# dspic.net
KiCad netlist of a schematic drawn in EAGLE
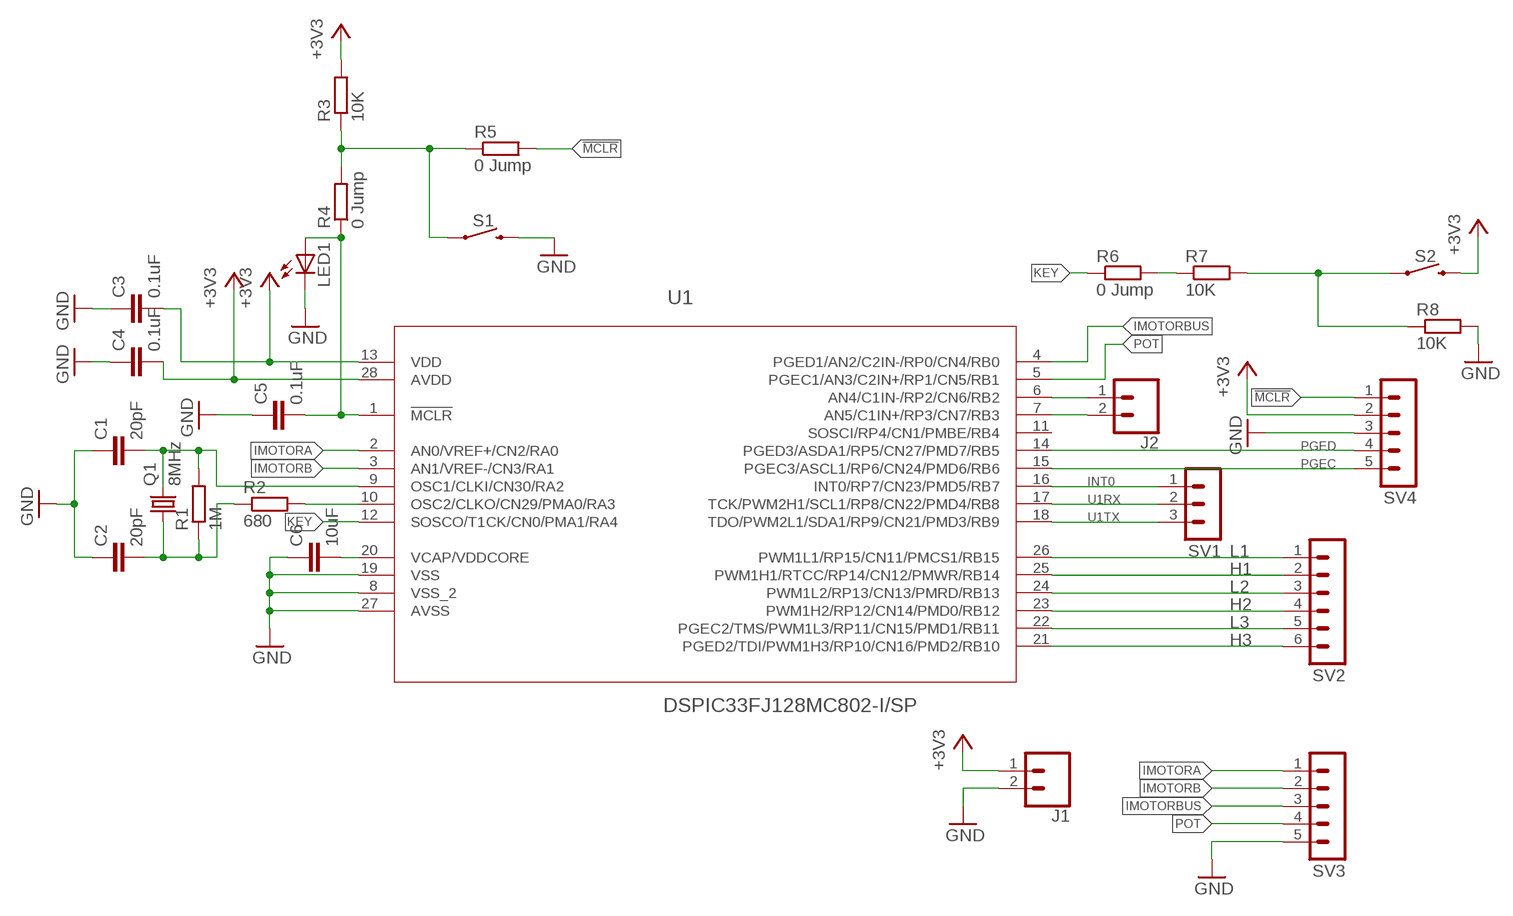
[diagram p0: schematic, sheet 1]

(export (version "E")
  (design (tool "Eeschema 10.0.6"))
  (components
    (comp (ref "C1")
      (value "20pF")
      (footprint "eagle-import:C025-024X044")
      (libsource (lib "eagle-import") (part "C-EU025-024X044"))
    )
    (comp (ref "C2")
      (value "20pF")
      (footprint "eagle-import:C025-024X044")
      (libsource (lib "eagle-import") (part "C-EU025-024X044"))
    )
    (comp (ref "C3")
      (value "0.1uF")
      (footprint "eagle-import:C025-024X044")
      (libsource (lib "eagle-import") (part "C-EU025-024X044"))
    )
    (comp (ref "C4")
      (value "0.1uF")
      (footprint "eagle-import:C025-024X044")
      (libsource (lib "eagle-import") (part "C-EU025-024X044"))
    )
    (comp (ref "C5")
      (value "0.1uF")
      (footprint "eagle-import:C025-024X044")
      (libsource (lib "eagle-import") (part "C-EU025-024X044"))
    )
    (comp (ref "C6")
      (value "10uF")
      (footprint "eagle-import:C025-024X044")
      (libsource (lib "eagle-import") (part "C-EU025-024X044"))
    )
    (comp (ref "J1")
      (value "CONN_02")
      (footprint "eagle-import:1X02")
      (libsource (lib "eagle-import") (part "CONN_02"))
    )
    (comp (ref "J2")
      (value "CONN_02")
      (footprint "eagle-import:1X02")
      (libsource (lib "eagle-import") (part "CONN_02"))
    )
    (comp (ref "LED1")
      (value "LED3MM")
      (footprint "eagle-import:LED3MM")
      (libsource (lib "eagle-import") (part "LED3MM"))
    )
    (comp (ref "Q1")
      (value "8MHz")
      (footprint "eagle-import:HC49_S")
      (libsource (lib "eagle-import") (part "CRYSTALHC49S"))
    )
    (comp (ref "R1")
      (value "1M")
      (footprint "eagle-import:0207_10")
      (libsource (lib "eagle-import") (part "R-EU_0207/10"))
    )
    (comp (ref "R2")
      (value "680")
      (footprint "eagle-import:0207_10")
      (libsource (lib "eagle-import") (part "R-EU_0207/10"))
    )
    (comp (ref "R3")
      (value "10K")
      (footprint "eagle-import:0207_10")
      (libsource (lib "eagle-import") (part "R-EU_0207/10"))
    )
    (comp (ref "R4")
      (value "0 Jump")
      (footprint "eagle-import:0207_10")
      (libsource (lib "eagle-import") (part "R-EU_0207/10"))
    )
    (comp (ref "R5")
      (value "0 Jump")
      (footprint "eagle-import:0207_10")
      (libsource (lib "eagle-import") (part "R-EU_0207/10"))
    )
    (comp (ref "R6")
      (value "0 Jump")
      (footprint "eagle-import:0207_10")
      (libsource (lib "eagle-import") (part "R-EU_0207/10"))
    )
    (comp (ref "R7")
      (value "10K")
      (footprint "eagle-import:0207_10")
      (libsource (lib "eagle-import") (part "R-EU_0207/10"))
    )
    (comp (ref "R8")
      (value "10K")
      (footprint "eagle-import:0207_10")
      (libsource (lib "eagle-import") (part "R-EU_0207/10"))
    )
    (comp (ref "S1")
      (value "MOMENTARY-SWITCH-SPST-PTH-6.0MM")
      (footprint "eagle-import:TACTILE_SWITCH_PTH_6.0MM")
      (libsource (lib "eagle-import") (part "MOMENTARY-SWITCH-SPST-PTH-6.0MM"))
    )
    (comp (ref "S2")
      (value "MOMENTARY-SWITCH-SPST-PTH-6.0MM")
      (footprint "eagle-import:TACTILE_SWITCH_PTH_6.0MM")
      (libsource (lib "eagle-import") (part "MOMENTARY-SWITCH-SPST-PTH-6.0MM"))
    )
    (comp (ref "SV1")
      (value "MA03-1")
      (footprint "eagle-import:MA03-1")
      (libsource (lib "eagle-import") (part "MA03-1"))
    )
    (comp (ref "SV2")
      (value "MA06-1")
      (footprint "eagle-import:MA06-1")
      (libsource (lib "eagle-import") (part "MA06-1"))
    )
    (comp (ref "SV3")
      (value "MA05-1")
      (footprint "eagle-import:MA05-1")
      (libsource (lib "eagle-import") (part "MA05-1"))
    )
    (comp (ref "SV4")
      (value "MA05-1")
      (footprint "eagle-import:MA05-1")
      (libsource (lib "eagle-import") (part "MA05-1"))
    )
    (comp (ref "U1")
      (value "DSPIC33FJ128MC802-I/SP")
      (footprint "eagle-import:DIP254P762X508-28")
      (libsource (lib "eagle-import") (part "DSPIC33FJ128MC802-I/SP"))
    )
  )
  (nets
    (net (code "1") (name "+3V3") (class "Default")
      (node (ref "C3") (pin "2") (pinfunction "2_2") (pintype "passive"))
      (node (ref "C4") (pin "2") (pinfunction "2_2") (pintype "passive"))
      (node (ref "J1") (pin "1") (pinfunction "1_1") (pintype "passive"))
      (node (ref "R3") (pin "2") (pinfunction "2_2") (pintype "passive"))
      (node (ref "S2") (pin "3") (pinfunction "2_3") (pintype "passive"))
      (node (ref "SV4") (pin "2") (pinfunction "2_2") (pintype "passive"))
      (node (ref "U1") (pin "13") (pinfunction "VDD_13") (pintype "power_in"))
      (node (ref "U1") (pin "28") (pinfunction "AVDD_28") (pintype "power_in"))
    )
    (net (code "2") (name "/H1") (class "Default")
      (node (ref "SV2") (pin "2") (pinfunction "2_2") (pintype "passive"))
      (node (ref "U1") (pin "25") (pinfunction "PWM1H1/RTCC/RP14/CN12/PMWR/RB14_25") (pintype "bidirectional"))
    )
    (net (code "3") (name "/H2") (class "Default")
      (node (ref "SV2") (pin "4") (pinfunction "4_4") (pintype "passive"))
      (node (ref "U1") (pin "23") (pinfunction "PWM1H2/RP12/CN14/PMD0/RB12_23") (pintype "bidirectional"))
    )
    (net (code "4") (name "/H3") (class "Default")
      (node (ref "SV2") (pin "6") (pinfunction "6_6") (pintype "passive"))
      (node (ref "U1") (pin "21") (pinfunction "PGED2/TDI/PWM1H3/RP10/CN16/PMD2/RB10_21") (pintype "bidirectional"))
    )
    (net (code "5") (name "/INT0") (class "Default")
      (node (ref "SV1") (pin "1") (pinfunction "1_1") (pintype "passive"))
      (node (ref "U1") (pin "16") (pinfunction "INT0/RP7/CN23/PMD5/RB7_16") (pintype "bidirectional"))
    )
    (net (code "6") (name "/L1") (class "Default")
      (node (ref "SV2") (pin "1") (pinfunction "1_1") (pintype "passive"))
      (node (ref "U1") (pin "26") (pinfunction "PWM1L1/RP15/CN11/PMCS1/RB15_26") (pintype "bidirectional"))
    )
    (net (code "7") (name "/L2") (class "Default")
      (node (ref "SV2") (pin "3") (pinfunction "3_3") (pintype "passive"))
      (node (ref "U1") (pin "24") (pinfunction "PWM1L2/RP13/CN13/PMRD/RB13_24") (pintype "bidirectional"))
    )
    (net (code "8") (name "/L3") (class "Default")
      (node (ref "SV2") (pin "5") (pinfunction "5_5") (pintype "passive"))
      (node (ref "U1") (pin "22") (pinfunction "PGEC2/TMS/PWM1L3/RP11/CN15/PMD1/RB11_22") (pintype "bidirectional"))
    )
    (net (code "9") (name "/PGEC") (class "Default")
      (node (ref "SV4") (pin "5") (pinfunction "5_5") (pintype "passive"))
      (node (ref "U1") (pin "15") (pinfunction "PGEC3/ASCL1/RP6/CN24/PMD6/RB6_15") (pintype "bidirectional"))
    )
    (net (code "10") (name "/PGED") (class "Default")
      (node (ref "SV4") (pin "4") (pinfunction "4_4") (pintype "passive"))
      (node (ref "U1") (pin "14") (pinfunction "PGED3/ASDA1/RP5/CN27/PMD7/RB5_14") (pintype "bidirectional"))
    )
    (net (code "11") (name "/U1RX") (class "Default")
      (node (ref "SV1") (pin "2") (pinfunction "2_2") (pintype "passive"))
      (node (ref "U1") (pin "17") (pinfunction "TCK/PWM2H1/SCL1/RP8/CN22/PMD4/RB8_17") (pintype "bidirectional"))
    )
    (net (code "12") (name "/U1TX") (class "Default")
      (node (ref "SV1") (pin "3") (pinfunction "3_3") (pintype "passive"))
      (node (ref "U1") (pin "18") (pinfunction "TDO/PWM2L1/SDA1/RP9/CN21/PMD3/RB9_18") (pintype "bidirectional"))
    )
    (net (code "13") (name "/~{MCLR}") (class "Default")
      (node (ref "R5") (pin "2") (pinfunction "2_2") (pintype "passive"))
      (node (ref "SV4") (pin "1") (pinfunction "1_1") (pintype "passive"))
    )
    (net (code "14") (name "GND") (class "Default")
      (node (ref "C1") (pin "1") (pinfunction "1_1") (pintype "passive"))
      (node (ref "C2") (pin "1") (pinfunction "1_1") (pintype "passive"))
      (node (ref "C3") (pin "1") (pinfunction "1_1") (pintype "passive"))
      (node (ref "C4") (pin "1") (pinfunction "1_1") (pintype "passive"))
      (node (ref "C5") (pin "1") (pinfunction "1_1") (pintype "passive"))
      (node (ref "C6") (pin "1") (pinfunction "1_1") (pintype "passive"))
      (node (ref "J1") (pin "2") (pinfunction "2_2") (pintype "passive"))
      (node (ref "LED1") (pin "K") (pinfunction "C_K") (pintype "passive"))
      (node (ref "R8") (pin "2") (pinfunction "2_2") (pintype "passive"))
      (node (ref "S1") (pin "3") (pinfunction "2_3") (pintype "passive"))
      (node (ref "SV3") (pin "5") (pinfunction "5_5") (pintype "passive"))
      (node (ref "SV4") (pin "3") (pinfunction "3_3") (pintype "passive"))
      (node (ref "U1") (pin "19") (pinfunction "VSS_19") (pintype "power_in"))
      (node (ref "U1") (pin "27") (pinfunction "AVSS_27") (pintype "power_in"))
      (node (ref "U1") (pin "8") (pinfunction "VSS_2_8") (pintype "power_in"))
    )
    (net (code "15") (name "IMOTORA") (class "Default")
      (node (ref "SV3") (pin "1") (pinfunction "1_1") (pintype "passive"))
      (node (ref "U1") (pin "2") (pinfunction "AN0/VREF+/CN2/RA0_2") (pintype "bidirectional"))
    )
    (net (code "16") (name "IMOTORB") (class "Default")
      (node (ref "SV3") (pin "2") (pinfunction "2_2") (pintype "passive"))
      (node (ref "U1") (pin "3") (pinfunction "AN1/VREF-/CN3/RA1_3") (pintype "bidirectional"))
    )
    (net (code "17") (name "IMOTORBUS") (class "Default")
      (node (ref "SV3") (pin "3") (pinfunction "3_3") (pintype "passive"))
      (node (ref "U1") (pin "4") (pinfunction "PGED1/AN2/C2IN-/RP0/CN4/RB0_4") (pintype "bidirectional"))
    )
    (net (code "18") (name "KEY") (class "Default")
      (node (ref "R6") (pin "1") (pinfunction "1_1") (pintype "passive"))
      (node (ref "U1") (pin "12") (pinfunction "SOSCO/T1CK/CN0/PMA1/RA4_12") (pintype "bidirectional"))
    )
    (net (code "19") (name "Net-(C2-Pad2)") (class "Default")
      (node (ref "C2") (pin "2") (pinfunction "2_2") (pintype "passive"))
      (node (ref "Q1") (pin "1") (pinfunction "1_1") (pintype "passive"))
      (node (ref "R1") (pin "1") (pinfunction "1_1") (pintype "passive"))
      (node (ref "R2") (pin "1") (pinfunction "1_1") (pintype "passive"))
    )
    (net (code "20") (name "Net-(R3-Pad1)") (class "Default")
      (node (ref "R3") (pin "1") (pinfunction "1_1") (pintype "passive"))
      (node (ref "R4") (pin "2") (pinfunction "2_2") (pintype "passive"))
      (node (ref "R5") (pin "1") (pinfunction "1_1") (pintype "passive"))
      (node (ref "S1") (pin "1") (pinfunction "1_1") (pintype "passive"))
    )
    (net (code "21") (name "Net-(R6-Pad2)") (class "Default")
      (node (ref "R6") (pin "2") (pinfunction "2_2") (pintype "passive"))
      (node (ref "R7") (pin "1") (pinfunction "1_1") (pintype "passive"))
    )
    (net (code "22") (name "Net-(R7-Pad2)") (class "Default")
      (node (ref "R7") (pin "2") (pinfunction "2_2") (pintype "passive"))
      (node (ref "R8") (pin "1") (pinfunction "1_1") (pintype "passive"))
      (node (ref "S2") (pin "1") (pinfunction "1_1") (pintype "passive"))
    )
    (net (code "23") (name "Net-(U1-AN4{slash}C1IN-{slash}RP2{slash}CN6{slash}RB2)") (class "Default")
      (node (ref "J2") (pin "1") (pinfunction "1_1") (pintype "passive"))
      (node (ref "U1") (pin "6") (pinfunction "AN4/C1IN-/RP2/CN6/RB2_6") (pintype "bidirectional"))
    )
    (net (code "24") (name "Net-(U1-AN5{slash}C1IN+{slash}RP3{slash}CN7{slash}RB3)") (class "Default")
      (node (ref "J2") (pin "2") (pinfunction "2_2") (pintype "passive"))
      (node (ref "U1") (pin "7") (pinfunction "AN5/C1IN+/RP3/CN7/RB3_7") (pintype "bidirectional"))
    )
    (net (code "25") (name "Net-(U1-OSC1{slash}CLKI{slash}CN30{slash}RA2)") (class "Default")
      (node (ref "C1") (pin "2") (pinfunction "2_2") (pintype "passive"))
      (node (ref "Q1") (pin "2") (pinfunction "2_2") (pintype "passive"))
      (node (ref "R1") (pin "2") (pinfunction "2_2") (pintype "passive"))
      (node (ref "U1") (pin "9") (pinfunction "OSC1/CLKI/CN30/RA2_9") (pintype "bidirectional"))
    )
    (net (code "26") (name "Net-(U1-OSC2{slash}CLKO{slash}CN29{slash}PMA0{slash}RA3)") (class "Default")
      (node (ref "R2") (pin "2") (pinfunction "2_2") (pintype "passive"))
      (node (ref "U1") (pin "10") (pinfunction "OSC2/CLKO/CN29/PMA0/RA3_10") (pintype "bidirectional"))
    )
    (net (code "27") (name "Net-(U1-VCAP{slash}VDDCORE)") (class "Default")
      (node (ref "C6") (pin "2") (pinfunction "2_2") (pintype "passive"))
      (node (ref "U1") (pin "20") (pinfunction "VCAP/VDDCORE_20") (pintype "power_in"))
    )
    (net (code "28") (name "Net-(U1-~{MCLR})") (class "Default")
      (node (ref "C5") (pin "2") (pinfunction "2_2") (pintype "passive"))
      (node (ref "LED1") (pin "A") (pinfunction "A_A") (pintype "passive"))
      (node (ref "R4") (pin "1") (pinfunction "1_1") (pintype "passive"))
      (node (ref "U1") (pin "1") (pinfunction "~{MCLR}_1") (pintype "input"))
    )
    (net (code "29") (name "POT") (class "Default")
      (node (ref "SV3") (pin "4") (pinfunction "4_4") (pintype "passive"))
      (node (ref "U1") (pin "5") (pinfunction "PGEC1/AN3/C2IN+/RP1/CN5/RB1_5") (pintype "bidirectional"))
    )
    (net (code "30") (name "unconnected-(U1-SOSCI{slash}RP4{slash}CN1{slash}PMBE{slash}RB4-Pad11)") (class "Default")
      (node (ref "U1") (pin "11") (pinfunction "SOSCI/RP4/CN1/PMBE/RB4_11") (pintype "bidirectional"))
    )
  )
)
